# Schematic.net
KiCad netlist of a schematic drawn in EAGLE
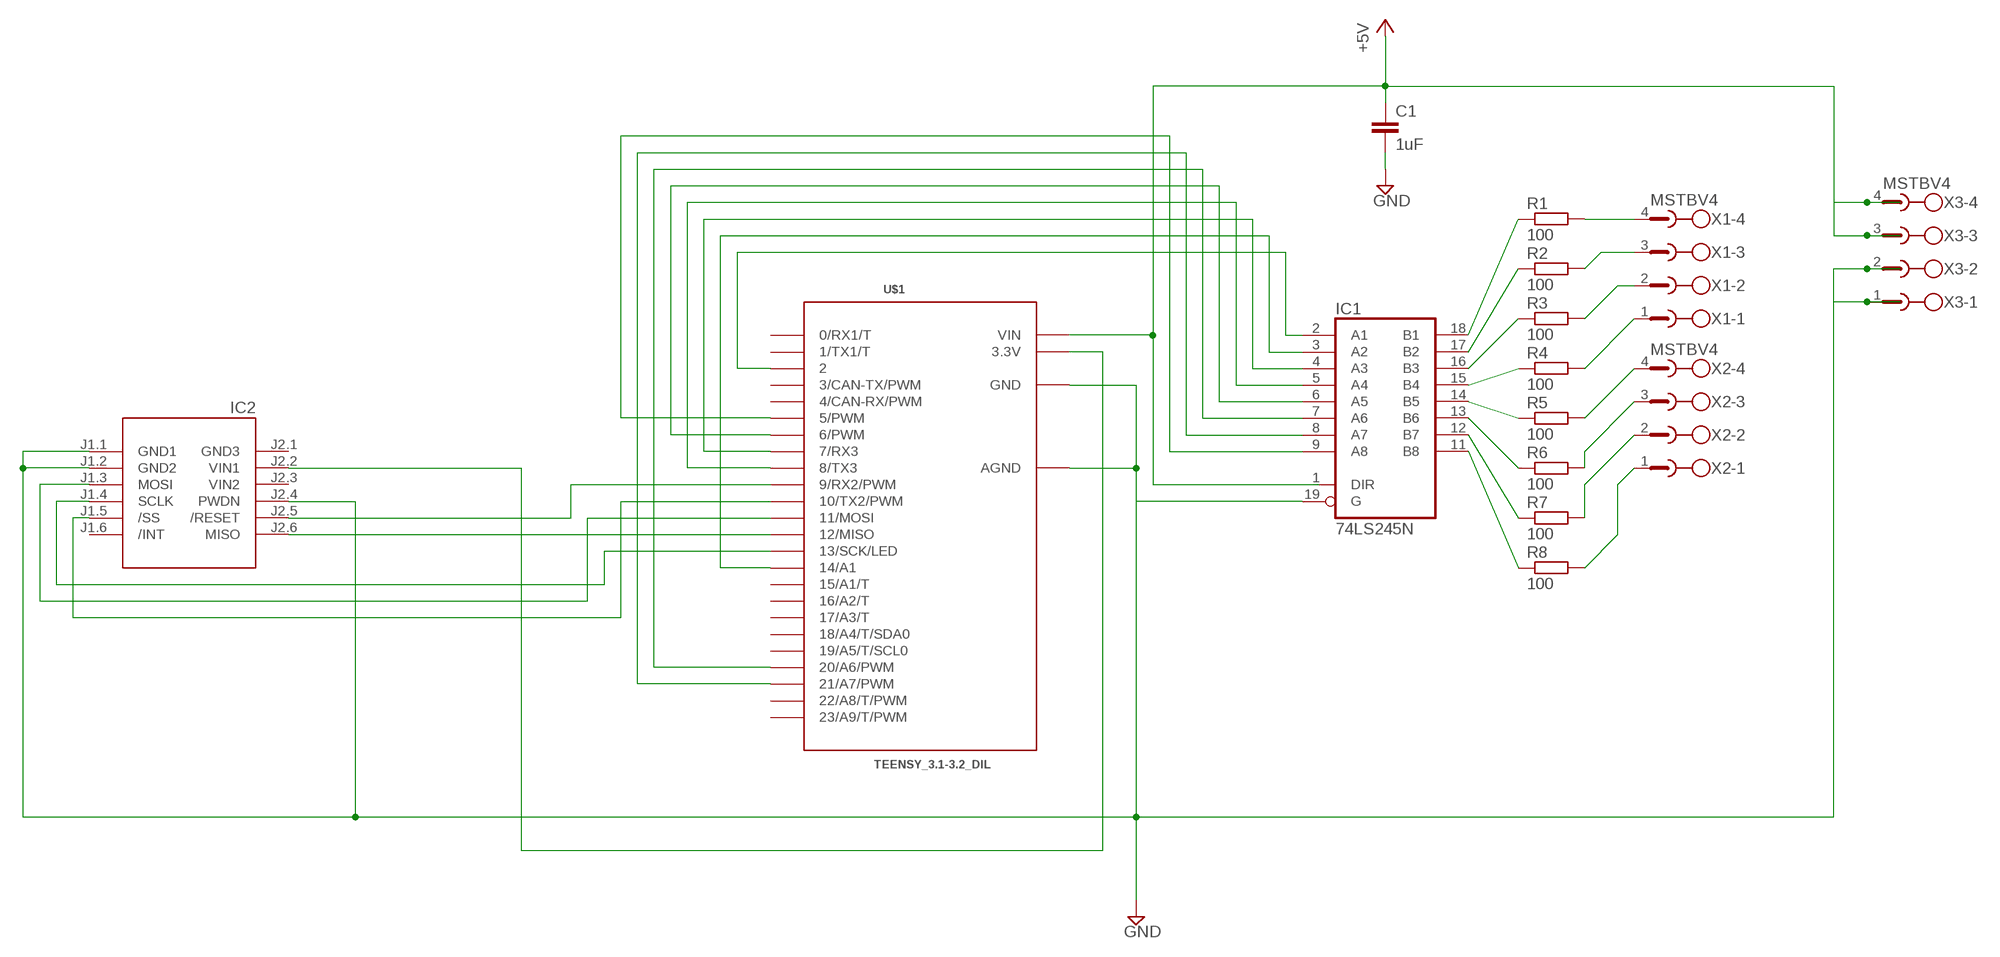
[diagram p0: schematic, sheet 1]

(export (version "E")
  (design (tool "Eeschema 10.0.6"))
  (components
    (comp (ref "C1")
      (value "1uF")
      (footprint "eagle-import:C050-035X075")
      (libsource (lib "eagle-import") (part "C-EU050-035X075"))
    )
    (comp (ref "IC1")
      (value "74LS245N")
      (footprint "eagle-import:DIL20")
      (libsource (lib "eagle-import") (part "74245NLS"))
    )
    (comp (ref "IC2")
      (value "WIZ820IO_DEVICE'DUAL-IN-LINE'")
      (footprint "eagle-import:WIZ820IO")
      (libsource (lib "eagle-import") (part "WIZ820IO_DEVICE'DUAL-IN-LINE'"))
    )
    (comp (ref "R1")
      (value "100")
      (footprint "eagle-import:0207_7")
      (libsource (lib "eagle-import") (part "R-EU_0207/7"))
    )
    (comp (ref "R2")
      (value "100")
      (footprint "eagle-import:0207_7")
      (libsource (lib "eagle-import") (part "R-EU_0207/7"))
    )
    (comp (ref "R3")
      (value "100")
      (footprint "eagle-import:0207_7")
      (libsource (lib "eagle-import") (part "R-EU_0207/7"))
    )
    (comp (ref "R4")
      (value "100")
      (footprint "eagle-import:0207_7")
      (libsource (lib "eagle-import") (part "R-EU_0207/7"))
    )
    (comp (ref "R5")
      (value "100")
      (footprint "eagle-import:0207_7")
      (libsource (lib "eagle-import") (part "R-EU_0207/7"))
    )
    (comp (ref "R6")
      (value "100")
      (footprint "eagle-import:0207_7")
      (libsource (lib "eagle-import") (part "R-EU_0207/7"))
    )
    (comp (ref "R7")
      (value "100")
      (footprint "eagle-import:0207_7")
      (libsource (lib "eagle-import") (part "R-EU_0207/7"))
    )
    (comp (ref "R8")
      (value "100")
      (footprint "eagle-import:0207_7")
      (libsource (lib "eagle-import") (part "R-EU_0207/7"))
    )
    (comp (ref "U$1")
      (value "TEENSY_3.1-3.2_DIL")
      (footprint "eagle-import:TEENSY_3.0-3.2&LC_DIL")
      (libsource (lib "eagle-import") (part "TEENSY_3.1-3.2_DIL"))
    )
    (comp (ref "X1")
      (value "MSTBV4")
      (footprint "eagle-import:MSTBV4")
      (fields (field (name "MPN") "MSTBV 2,5/4-GF-5.08"))
      (libsource (lib "eagle-import") (part "MSTBV4"))
    )
    (comp (ref "X2")
      (value "MSTBV4")
      (footprint "eagle-import:MSTBV4")
      (fields (field (name "MPN") "MSTBV 2,5/4-GF-5.08"))
      (libsource (lib "eagle-import") (part "MSTBV4"))
    )
    (comp (ref "X3")
      (value "MSTBV4")
      (footprint "eagle-import:MSTBV4")
      (fields (field (name "MPN") "MSTBV 2,5/4-GF-5.08"))
      (libsource (lib "eagle-import") (part "MSTBV4"))
    )
  )
  (nets
    (net (code "1") (name "+5V") (class "Default")
      (node (ref "C1") (pin "1") (pinfunction "1_1") (pintype "passive"))
      (node (ref "U$1") (pin "VIN") (pinfunction "VIN_VIN") (pintype "power_in"))
      (node (ref "X3") (pin "3") (pinfunction "1_3") (pintype "passive"))
      (node (ref "X3") (pin "4") (pinfunction "1_4") (pintype "passive"))
    )
    (net (code "2") (name "/GND3") (class "Default")
      (node (ref "IC2") (pin "J2.1") (pinfunction "GND3_J2.1") (pintype "power_in"))
    )
    (net (code "3") (name "/VIN2") (class "Default")
      (node (ref "IC2") (pin "J2.3") (pinfunction "VIN2_J2.3") (pintype "power_in"))
    )
    (net (code "4") (name "GND") (class "Default")
      (node (ref "C1") (pin "2") (pinfunction "2_2") (pintype "passive"))
      (node (ref "IC1") (pin "19") (pinfunction "G_19") (pintype "input"))
      (node (ref "IC2") (pin "J1.1") (pinfunction "GND1_J1.1") (pintype "power_in"))
      (node (ref "IC2") (pin "J1.2") (pinfunction "GND2_J1.2") (pintype "power_in"))
      (node (ref "IC2") (pin "J2.4") (pinfunction "PWDN_J2.4") (pintype "input"))
      (node (ref "U$1") (pin "AGND") (pinfunction "AGND_AGND") (pintype "power_in"))
      (node (ref "U$1") (pin "GND") (pinfunction "GND_GND") (pintype "power_in"))
      (node (ref "X3") (pin "1") (pinfunction "1_1") (pintype "passive"))
      (node (ref "X3") (pin "2") (pinfunction "1_2") (pintype "passive"))
    )
    (net (code "5") (name "Net-(IC1A-A1)") (class "Default")
      (node (ref "IC1") (pin "2") (pinfunction "A1_2") (pintype "bidirectional"))
      (node (ref "U$1") (pin "2") (pinfunction "2_2") (pintype "bidirectional"))
    )
    (net (code "6") (name "Net-(IC1A-A2)") (class "Default")
      (node (ref "IC1") (pin "3") (pinfunction "A2_3") (pintype "bidirectional"))
      (node (ref "U$1") (pin "14/A0") (pinfunction "14/A1_14/A0") (pintype "bidirectional"))
    )
    (net (code "7") (name "Net-(IC1A-A3)") (class "Default")
      (node (ref "IC1") (pin "4") (pinfunction "A3_4") (pintype "bidirectional"))
      (node (ref "U$1") (pin "7") (pinfunction "7/RX3_7") (pintype "bidirectional"))
    )
    (net (code "8") (name "Net-(IC1A-A4)") (class "Default")
      (node (ref "IC1") (pin "5") (pinfunction "A4_5") (pintype "bidirectional"))
      (node (ref "U$1") (pin "8") (pinfunction "8/TX3_8") (pintype "bidirectional"))
    )
    (net (code "9") (name "Net-(IC1A-A5)") (class "Default")
      (node (ref "IC1") (pin "6") (pinfunction "A5_6") (pintype "bidirectional"))
      (node (ref "U$1") (pin "6") (pinfunction "6/PWM_6") (pintype "bidirectional"))
    )
    (net (code "10") (name "Net-(IC1A-A6)") (class "Default")
      (node (ref "IC1") (pin "7") (pinfunction "A6_7") (pintype "bidirectional"))
      (node (ref "U$1") (pin "20/A6") (pinfunction "20/A6/PWM_20/A6") (pintype "bidirectional"))
    )
    (net (code "11") (name "Net-(IC1A-A7)") (class "Default")
      (node (ref "IC1") (pin "8") (pinfunction "A7_8") (pintype "bidirectional"))
      (node (ref "U$1") (pin "21/A7") (pinfunction "21/A7/PWM_21/A7") (pintype "bidirectional"))
    )
    (net (code "12") (name "Net-(IC1A-A8)") (class "Default")
      (node (ref "IC1") (pin "9") (pinfunction "A8_9") (pintype "bidirectional"))
      (node (ref "U$1") (pin "5") (pinfunction "5/PWM_5") (pintype "bidirectional"))
    )
    (net (code "13") (name "Net-(IC1A-B1)") (class "Default")
      (node (ref "IC1") (pin "18") (pinfunction "B1_18") (pintype "bidirectional"))
      (node (ref "R1") (pin "1") (pinfunction "1_1") (pintype "passive"))
    )
    (net (code "14") (name "Net-(IC1A-B2)") (class "Default")
      (node (ref "IC1") (pin "17") (pinfunction "B2_17") (pintype "bidirectional"))
      (node (ref "R2") (pin "1") (pinfunction "1_1") (pintype "passive"))
    )
    (net (code "15") (name "Net-(IC1A-B3)") (class "Default")
      (node (ref "IC1") (pin "16") (pinfunction "B3_16") (pintype "bidirectional"))
      (node (ref "R3") (pin "1") (pinfunction "1_1") (pintype "passive"))
    )
    (net (code "16") (name "Net-(IC1A-B4)") (class "Default")
      (node (ref "IC1") (pin "15") (pinfunction "B4_15") (pintype "bidirectional"))
      (node (ref "R4") (pin "1") (pinfunction "1_1") (pintype "passive"))
    )
    (net (code "17") (name "Net-(IC1A-B5)") (class "Default")
      (node (ref "IC1") (pin "14") (pinfunction "B5_14") (pintype "bidirectional"))
      (node (ref "R5") (pin "1") (pinfunction "1_1") (pintype "passive"))
    )
    (net (code "18") (name "Net-(IC1A-B6)") (class "Default")
      (node (ref "IC1") (pin "13") (pinfunction "B6_13") (pintype "bidirectional"))
      (node (ref "R6") (pin "1") (pinfunction "1_1") (pintype "passive"))
    )
    (net (code "19") (name "Net-(IC1A-B7)") (class "Default")
      (node (ref "IC1") (pin "12") (pinfunction "B7_12") (pintype "bidirectional"))
      (node (ref "R7") (pin "1") (pinfunction "1_1") (pintype "passive"))
    )
    (net (code "20") (name "Net-(IC1A-B8)") (class "Default")
      (node (ref "IC1") (pin "11") (pinfunction "B8_11") (pintype "bidirectional"))
      (node (ref "R8") (pin "1") (pinfunction "1_1") (pintype "passive"))
    )
    (net (code "21") (name "Net-(IC2-MISO)") (class "Default")
      (node (ref "IC2") (pin "J2.6") (pinfunction "MISO_J2.6") (pintype "output"))
      (node (ref "U$1") (pin "12") (pinfunction "12/MISO_12") (pintype "bidirectional"))
    )
    (net (code "22") (name "Net-(IC2-MOSI)") (class "Default")
      (node (ref "IC2") (pin "J1.3") (pinfunction "MOSI_J1.3") (pintype "input"))
      (node (ref "U$1") (pin "11") (pinfunction "11/MOSI_11") (pintype "bidirectional"))
    )
    (net (code "23") (name "Net-(IC2-SCLK)") (class "Default")
      (node (ref "IC2") (pin "J1.4") (pinfunction "SCLK_J1.4") (pintype "input"))
      (node (ref "U$1") (pin "13") (pinfunction "13/SCK/LED_13") (pintype "bidirectional"))
    )
    (net (code "24") (name "Net-(IC2-VIN1)") (class "Default")
      (node (ref "IC2") (pin "J2.2") (pinfunction "VIN1_J2.2") (pintype "power_in"))
      (node (ref "U$1") (pin "3.3V") (pinfunction "3.3V_3.3V") (pintype "power_in"))
    )
    (net (code "25") (name "Net-(IC2-{slash}RESET)") (class "Default")
      (node (ref "IC2") (pin "J2.5") (pinfunction "/RESET_J2.5") (pintype "input"))
      (node (ref "U$1") (pin "9") (pinfunction "9/RX2/PWM_9") (pintype "bidirectional"))
    )
    (net (code "26") (name "Net-(IC2-{slash}SS)") (class "Default")
      (node (ref "IC2") (pin "J1.5") (pinfunction "/SS_J1.5") (pintype "input"))
      (node (ref "U$1") (pin "10") (pinfunction "10/TX2/PWM_10") (pintype "bidirectional"))
    )
    (net (code "27") (name "Net-(R4-Pad2)") (class "Default")
      (node (ref "R4") (pin "2") (pinfunction "2_2") (pintype "passive"))
      (node (ref "X1") (pin "1") (pinfunction "1_1") (pintype "passive"))
    )
    (net (code "28") (name "Net-(R8-Pad2)") (class "Default")
      (node (ref "R8") (pin "2") (pinfunction "2_2") (pintype "passive"))
      (node (ref "X2") (pin "1") (pinfunction "1_1") (pintype "passive"))
    )
    (net (code "29") (name "Net-(X1B-1)") (class "Default")
      (node (ref "R3") (pin "2") (pinfunction "2_2") (pintype "passive"))
      (node (ref "X1") (pin "2") (pinfunction "1_2") (pintype "passive"))
    )
    (net (code "30") (name "Net-(X1C-1)") (class "Default")
      (node (ref "R2") (pin "2") (pinfunction "2_2") (pintype "passive"))
      (node (ref "X1") (pin "3") (pinfunction "1_3") (pintype "passive"))
    )
    (net (code "31") (name "Net-(X1D-1)") (class "Default")
      (node (ref "R1") (pin "2") (pinfunction "2_2") (pintype "passive"))
      (node (ref "X1") (pin "4") (pinfunction "1_4") (pintype "passive"))
    )
    (net (code "32") (name "Net-(X2B-1)") (class "Default")
      (node (ref "R7") (pin "2") (pinfunction "2_2") (pintype "passive"))
      (node (ref "X2") (pin "2") (pinfunction "1_2") (pintype "passive"))
    )
    (net (code "33") (name "Net-(X2C-1)") (class "Default")
      (node (ref "R6") (pin "2") (pinfunction "2_2") (pintype "passive"))
      (node (ref "X2") (pin "3") (pinfunction "1_3") (pintype "passive"))
    )
    (net (code "34") (name "Net-(X2D-1)") (class "Default")
      (node (ref "R5") (pin "2") (pinfunction "2_2") (pintype "passive"))
      (node (ref "X2") (pin "4") (pinfunction "1_4") (pintype "passive"))
    )
    (net (code "35") (name "unconnected-(IC1A-DIR-Pad1)") (class "Default")
      (node (ref "IC1") (pin "1") (pinfunction "DIR_1") (pintype "input"))
    )
    (net (code "36") (name "unconnected-(IC2-{slash}INT-PadJ1.6)") (class "Default")
      (node (ref "IC2") (pin "J1.6") (pinfunction "/INT_J1.6") (pintype "output"))
    )
    (net (code "37") (name "unconnected-(U$1-0{slash}RX1{slash}T-Pad0)") (class "Default")
      (node (ref "U$1") (pin "0") (pinfunction "0/RX1/T_0") (pintype "bidirectional"))
    )
    (net (code "38") (name "unconnected-(U$1-1{slash}TX1{slash}T-Pad1)") (class "Default")
      (node (ref "U$1") (pin "1") (pinfunction "1/TX1/T_1") (pintype "bidirectional"))
    )
    (net (code "39") (name "unconnected-(U$1-3{slash}CAN-TX{slash}PWM-Pad3)") (class "Default")
      (node (ref "U$1") (pin "3") (pinfunction "3/CAN-TX/PWM_3") (pintype "bidirectional"))
    )
    (net (code "40") (name "unconnected-(U$1-4{slash}CAN-RX{slash}PWM-Pad4)") (class "Default")
      (node (ref "U$1") (pin "4") (pinfunction "4/CAN-RX/PWM_4") (pintype "bidirectional"))
    )
    (net (code "41") (name "unconnected-(U$1-15{slash}A1{slash}T-Pad15{slash}A1)") (class "Default")
      (node (ref "U$1") (pin "15/A1") (pinfunction "15/A1/T_15/A1") (pintype "bidirectional"))
    )
    (net (code "42") (name "unconnected-(U$1-16{slash}A2{slash}T-Pad16{slash}A2)") (class "Default")
      (node (ref "U$1") (pin "16/A2") (pinfunction "16/A2/T_16/A2") (pintype "bidirectional"))
    )
    (net (code "43") (name "unconnected-(U$1-17{slash}A3{slash}T-Pad17{slash}A3)") (class "Default")
      (node (ref "U$1") (pin "17/A3") (pinfunction "17/A3/T_17/A3") (pintype "bidirectional"))
    )
    (net (code "44") (name "unconnected-(U$1-18{slash}A4{slash}T{slash}SDA0-Pad18{slash}A4)") (class "Default")
      (node (ref "U$1") (pin "18/A4") (pinfunction "18/A4/T/SDA0_18/A4") (pintype "bidirectional"))
    )
    (net (code "45") (name "unconnected-(U$1-19{slash}A5{slash}T{slash}SCL0-Pad19{slash}A5)") (class "Default")
      (node (ref "U$1") (pin "19/A5") (pinfunction "19/A5/T/SCL0_19/A5") (pintype "bidirectional"))
    )
    (net (code "46") (name "unconnected-(U$1-22{slash}A8{slash}T{slash}PWM-Pad22{slash}A8)") (class "Default")
      (node (ref "U$1") (pin "22/A8") (pinfunction "22/A8/T/PWM_22/A8") (pintype "bidirectional"))
    )
    (net (code "47") (name "unconnected-(U$1-23{slash}A9{slash}T{slash}PWM-Pad23{slash}A9)") (class "Default")
      (node (ref "U$1") (pin "23/A9") (pinfunction "23/A9/T/PWM_23/A9") (pintype "bidirectional"))
    )
  )
)
